# bat.net
KiCad netlist of a schematic drawn in EAGLE
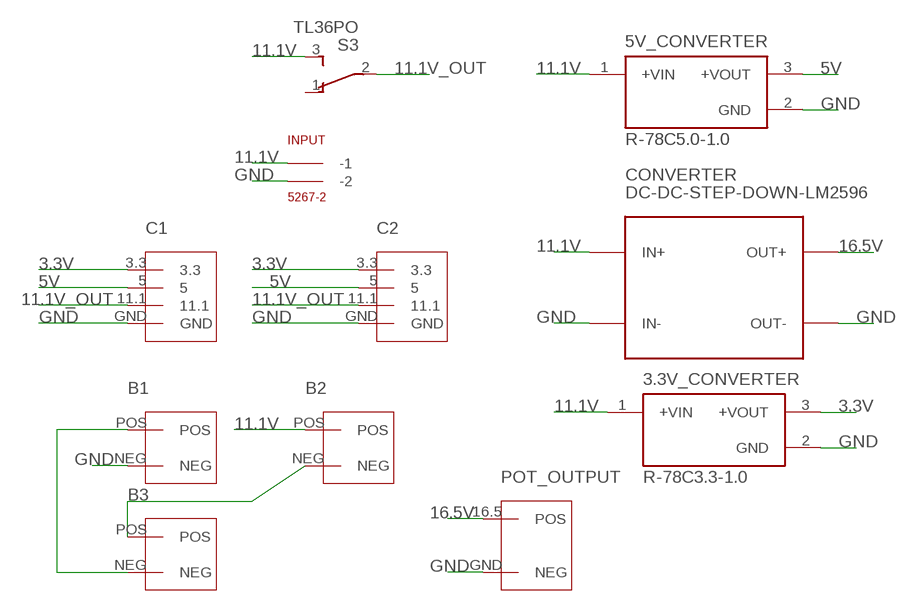
[diagram p0: schematic, sheet 1]

(export (version "E")
  (design (tool "Eeschema 10.0.6"))
  (components
    (comp (ref "3.3V_CONVERTER")
      (value "R-78C3.3-1.0")
      (footprint "eagle-import:CONV_R-78C5.0-1.0")
      (fields (field (name "MF") "Recom Power") (field (name "MP") "R-78C5.0-1.0"))
      (libsource (lib "eagle-import") (part "R-78C5.0-1.0"))
    )
    (comp (ref "5V_CONVERTER")
      (value "R-78C5.0-1.0")
      (footprint "eagle-import:CONV_R-78C5.0-1.0")
      (fields (field (name "MF") "Recom Power"))
      (libsource (lib "eagle-import") (part "R-78C5.0-1.0"))
    )
    (comp (ref "B1")
      (value "2_PIN_WIRE")
      (footprint "eagle-import:2_PIN_WIRE")
      (libsource (lib "eagle-import") (part "2_PIN_WIRE"))
    )
    (comp (ref "B2")
      (value "2_PIN_WIRE")
      (footprint "eagle-import:2_PIN_WIRE")
      (libsource (lib "eagle-import") (part "2_PIN_WIRE"))
    )
    (comp (ref "B3")
      (value "2_PIN_WIRE")
      (footprint "eagle-import:2_PIN_WIRE")
      (libsource (lib "eagle-import") (part "2_PIN_WIRE"))
    )
    (comp (ref "C1")
      (value "4_PIN_WIRE")
      (footprint "eagle-import:4_PIN_WIRE")
      (libsource (lib "eagle-import") (part "4_PIN_WIRE"))
    )
    (comp (ref "C2")
      (value "4_PIN_WIRE")
      (footprint "eagle-import:4_PIN_WIRE")
      (libsource (lib "eagle-import") (part "4_PIN_WIRE"))
    )
    (comp (ref "CONVERTER")
      (value "DC-DC-STEP-DOWN-LM2596")
      (footprint "eagle-import:DC-DC-STEP-DOWN-LM2596")
      (libsource (lib "eagle-import") (part "DC-DC-STEP-DOWN-LM2596"))
    )
    (comp (ref "INPUT")
      (value "5267-2")
      (footprint "eagle-import:5267-2")
      (libsource (lib "eagle-import") (part "5267-2"))
    )
    (comp (ref "POT_OUTPUT")
      (value "2_PIN_SMALL")
      (footprint "eagle-import:2_PIN_SMALL")
      (libsource (lib "eagle-import") (part "2_PIN_SMALL"))
    )
    (comp (ref "S3")
      (value "TL36PO")
      (footprint "eagle-import:TL3XPO")
      (libsource (lib "eagle-import") (part "TL36PO"))
    )
  )
  (nets
    (net (code "1") (name "/3.3V") (class "Default")
      (node (ref "3.3V_CONVERTER") (pin "3") (pinfunction "+VOUT_3") (pintype "output"))
      (node (ref "C1") (pin "3.3") (pinfunction "3.3_3.3") (pintype "bidirectional"))
      (node (ref "C2") (pin "3.3") (pinfunction "3.3_3.3") (pintype "bidirectional"))
    )
    (net (code "2") (name "/5V") (class "Default")
      (node (ref "5V_CONVERTER") (pin "3") (pinfunction "+VOUT_3") (pintype "output"))
      (node (ref "C1") (pin "5") (pinfunction "5_5") (pintype "bidirectional"))
      (node (ref "C2") (pin "5") (pinfunction "5_5") (pintype "bidirectional"))
    )
    (net (code "3") (name "/11.1V") (class "Default")
      (node (ref "3.3V_CONVERTER") (pin "1") (pinfunction "+VIN_1") (pintype "input"))
      (node (ref "5V_CONVERTER") (pin "1") (pinfunction "+VIN_1") (pintype "input"))
      (node (ref "B2") (pin "POS") (pinfunction "POS_POS") (pintype "bidirectional"))
      (node (ref "CONVERTER") (pin "IN+") (pinfunction "IN+_IN+") (pintype "bidirectional"))
      (node (ref "INPUT") (pin "P$1") (pinfunction "-1_P$1") (pintype "bidirectional"))
      (node (ref "S3") (pin "3") (pinfunction "S_3") (pintype "passive"))
    )
    (net (code "4") (name "/11.1V_OUT") (class "Default")
      (node (ref "C1") (pin "11.1") (pinfunction "11.1_11.1") (pintype "bidirectional"))
      (node (ref "C2") (pin "11.1") (pinfunction "11.1_11.1") (pintype "bidirectional"))
      (node (ref "S3") (pin "2") (pinfunction "P_2") (pintype "passive"))
    )
    (net (code "5") (name "/16.5V") (class "Default")
      (node (ref "CONVERTER") (pin "OUT+") (pinfunction "OUT+_OUT+") (pintype "bidirectional"))
      (node (ref "POT_OUTPUT") (pin "16.5") (pinfunction "POS_16.5") (pintype "bidirectional"))
    )
    (net (code "6") (name "/GND") (class "Default")
      (node (ref "3.3V_CONVERTER") (pin "2") (pinfunction "GND_2") (pintype "power_in"))
      (node (ref "5V_CONVERTER") (pin "2") (pinfunction "GND_2") (pintype "power_in"))
      (node (ref "B1") (pin "NEG") (pinfunction "NEG_NEG") (pintype "bidirectional"))
      (node (ref "C1") (pin "GND") (pinfunction "GND_GND") (pintype "bidirectional"))
      (node (ref "C2") (pin "GND") (pinfunction "GND_GND") (pintype "bidirectional"))
      (node (ref "CONVERTER") (pin "IN-") (pinfunction "IN-_IN-") (pintype "bidirectional"))
      (node (ref "CONVERTER") (pin "OUT-") (pinfunction "OUT-_OUT-") (pintype "bidirectional"))
      (node (ref "INPUT") (pin "P$2") (pinfunction "-2_P$2") (pintype "bidirectional"))
      (node (ref "POT_OUTPUT") (pin "GND") (pinfunction "NEG_GND") (pintype "bidirectional"))
    )
    (net (code "7") (name "Net-(B1-PadPOS)") (class "Default")
      (node (ref "B1") (pin "POS") (pinfunction "POS_POS") (pintype "bidirectional"))
      (node (ref "B3") (pin "NEG") (pinfunction "NEG_NEG") (pintype "bidirectional"))
    )
    (net (code "8") (name "Net-(B2-PadNEG)") (class "Default")
      (node (ref "B2") (pin "NEG") (pinfunction "NEG_NEG") (pintype "bidirectional"))
      (node (ref "B3") (pin "POS") (pinfunction "POS_POS") (pintype "bidirectional"))
    )
    (net (code "9") (name "unconnected-(S3-O-Pad1)") (class "Default")
      (node (ref "S3") (pin "1") (pinfunction "O_1") (pintype "passive"))
    )
  )
)
